# LCD.net
KiCad netlist of a schematic drawn in Altium Designer
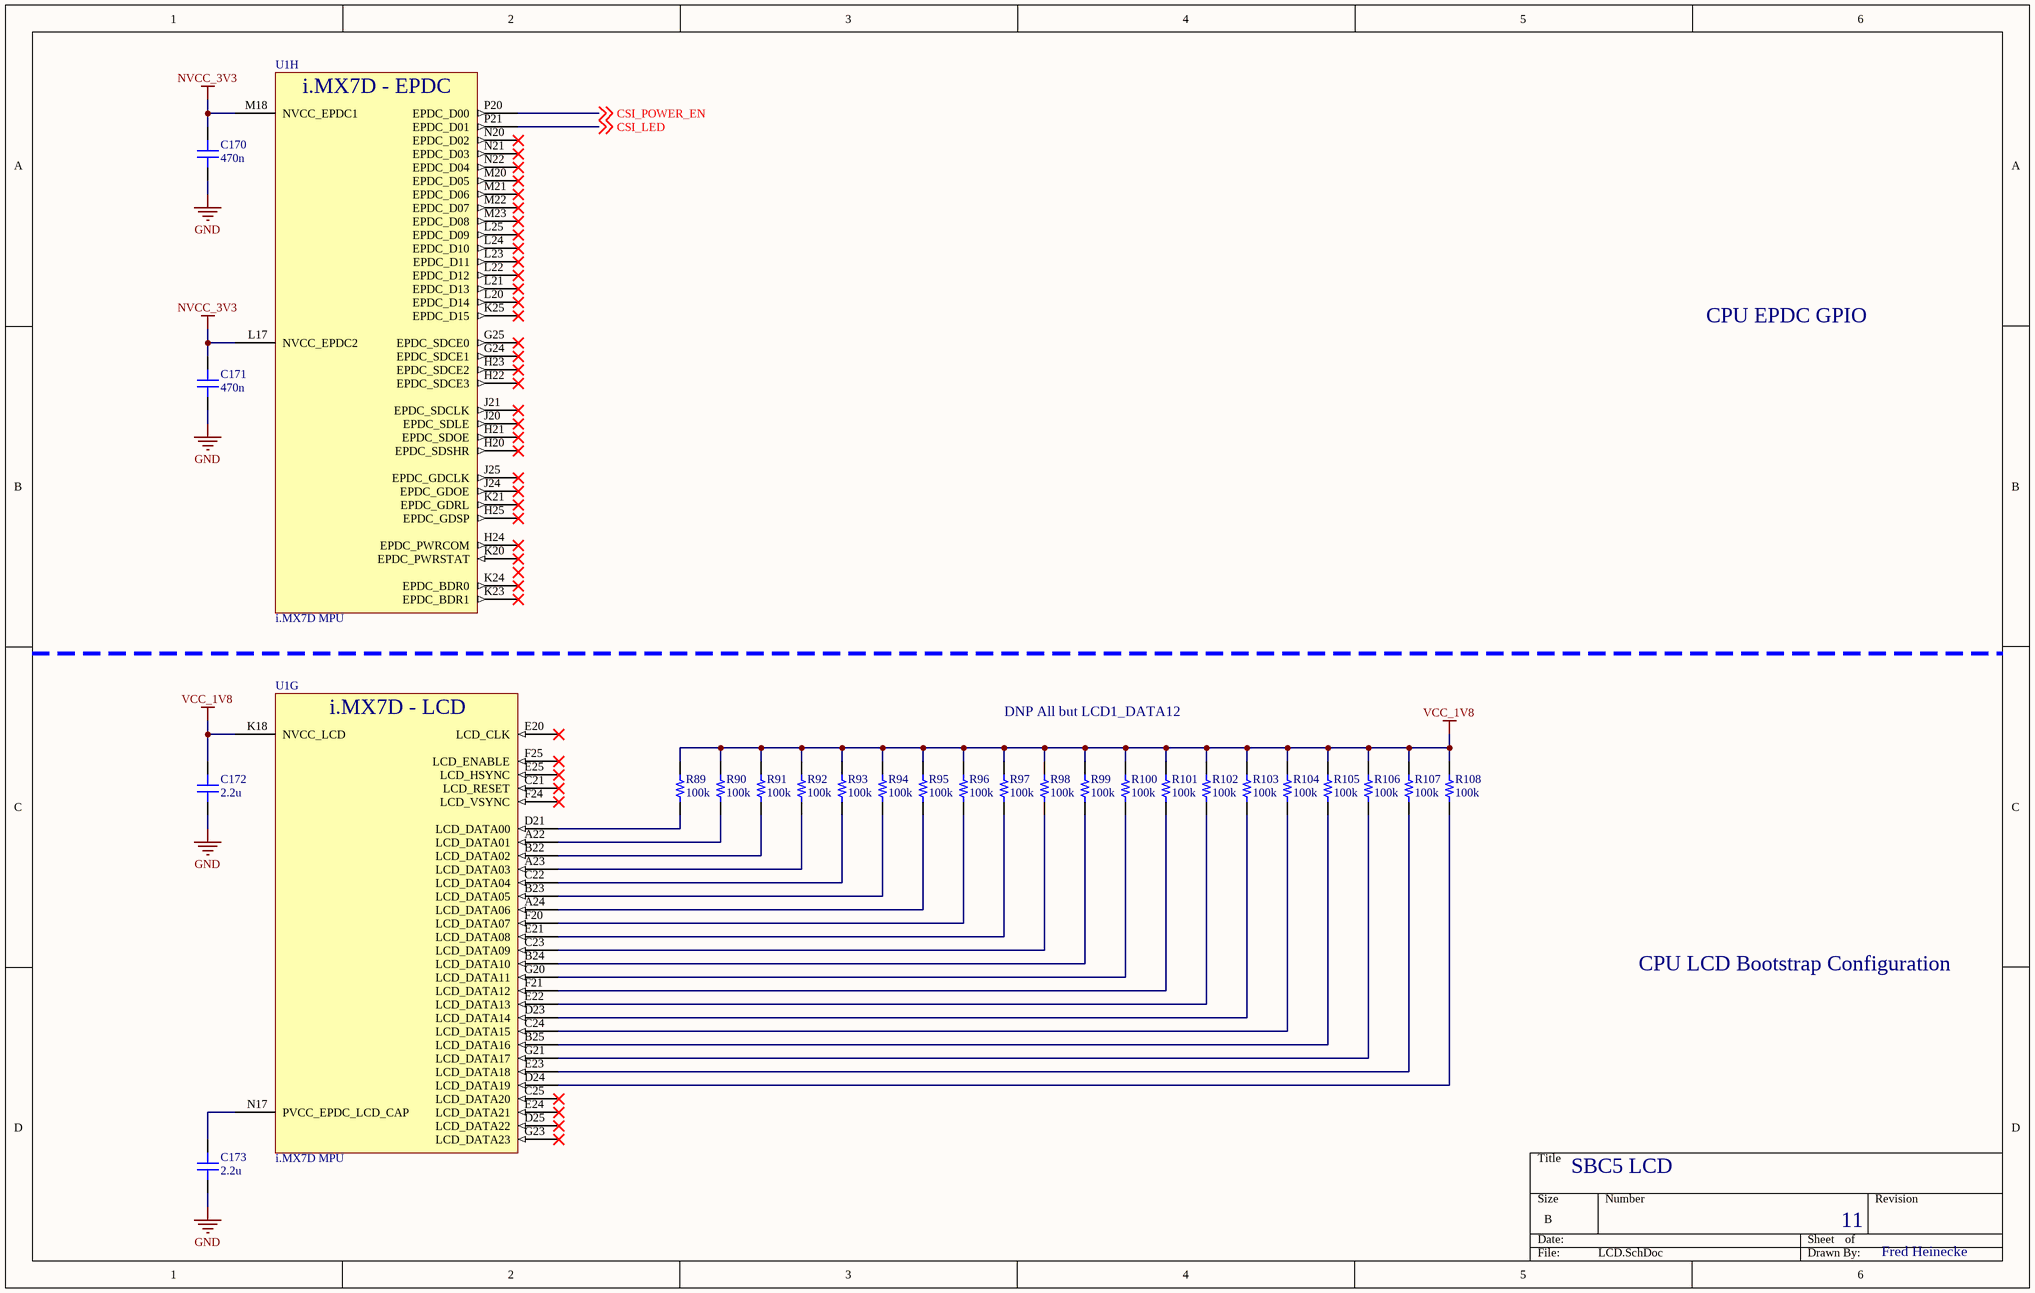
[diagram p0: LCD.SchDoc]

(export (version "E")
  (design (tool "Eeschema 10.0.6"))
  (components
    (comp (ref "C170")
      (value "470n")
      (footprint "C0402")
      (description "Cap Ceramic 0.47uF 10V X5R 10% SMD 0402 85C T/R")
      (fields
        (field (name "MANUFACTURER") "Samsung")
        (field (name "MANUFACTURER PART NUMBER") "CL05A474KP5NNNC")
      )
      (libsource (lib "SBC5") (part "CL05A474KP5NNNC"))
    )
    (comp (ref "C171")
      (value "470n")
      (footprint "C0402")
      (description "Cap Ceramic 0.47uF 10V X5R 10% SMD 0402 85C T/R")
      (fields
        (field (name "MANUFACTURER") "Samsung")
        (field (name "MANUFACTURER PART NUMBER") "CL05A474KP5NNNC")
      )
      (libsource (lib "SBC5") (part "CL05A474KP5NNNC"))
    )
    (comp (ref "C172")
      (value "2.2u")
      (footprint "C0402")
      (description "TAIYO YUDEN         LMK105BJ225MV-F            CERAMIC CAPACITOR, 2.2UF, 10V, X5R, 20%, 0402")
      (fields
        (field (name "MANUFACTURER") "Taiyo Yuden")
        (field (name "MANUFACTURER PART NUMBER") "LMK105BJ225MV-F")
      )
      (libsource (lib "SBC5") (part "LMK105BJ225MV-F"))
    )
    (comp (ref "C173")
      (value "2.2u")
      (footprint "C0402")
      (description "TAIYO YUDEN         LMK105BJ225MV-F            CERAMIC CAPACITOR, 2.2UF, 10V, X5R, 20%, 0402")
      (fields
        (field (name "MANUFACTURER") "Taiyo Yuden")
        (field (name "MANUFACTURER PART NUMBER") "LMK105BJ225MV-F")
      )
      (libsource (lib "SBC5") (part "LMK105BJ225MV-F"))
    )
    (comp (ref "R89")
      (value "100k")
      (footprint "R0201")
      (description "PANASONIC - ERJ1GNF1003C - RES, 100K, 1%, 0.05W, 0201, THICK FILM")
      (fields
        (field (name "MANUFACTURER") "Panasonic")
        (field (name "MANUFACTURER PART NUMBER") "ERJ-1GNF1003C")
      )
      (libsource (lib "SBC5") (part "ERJ-1GNF1003C"))
    )
    (comp (ref "R90")
      (value "100k")
      (footprint "R0201")
      (description "PANASONIC - ERJ1GNF1003C - RES, 100K, 1%, 0.05W, 0201, THICK FILM")
      (fields
        (field (name "MANUFACTURER") "Panasonic")
        (field (name "MANUFACTURER PART NUMBER") "ERJ-1GNF1003C")
      )
      (libsource (lib "SBC5") (part "ERJ-1GNF1003C"))
    )
    (comp (ref "R91")
      (value "100k")
      (footprint "R0201")
      (description "PANASONIC - ERJ1GNF1003C - RES, 100K, 1%, 0.05W, 0201, THICK FILM")
      (fields
        (field (name "MANUFACTURER") "Panasonic")
        (field (name "MANUFACTURER PART NUMBER") "ERJ-1GNF1003C")
      )
      (libsource (lib "SBC5") (part "ERJ-1GNF1003C"))
    )
    (comp (ref "R92")
      (value "100k")
      (footprint "R0201")
      (description "PANASONIC - ERJ1GNF1003C - RES, 100K, 1%, 0.05W, 0201, THICK FILM")
      (fields
        (field (name "MANUFACTURER") "Panasonic")
        (field (name "MANUFACTURER PART NUMBER") "ERJ-1GNF1003C")
      )
      (libsource (lib "SBC5") (part "ERJ-1GNF1003C"))
    )
    (comp (ref "R93")
      (value "100k")
      (footprint "R0201")
      (description "PANASONIC - ERJ1GNF1003C - RES, 100K, 1%, 0.05W, 0201, THICK FILM")
      (fields
        (field (name "MANUFACTURER") "Panasonic")
        (field (name "MANUFACTURER PART NUMBER") "ERJ-1GNF1003C")
      )
      (libsource (lib "SBC5") (part "ERJ-1GNF1003C"))
    )
    (comp (ref "R94")
      (value "100k")
      (footprint "R0201")
      (description "PANASONIC - ERJ1GNF1003C - RES, 100K, 1%, 0.05W, 0201, THICK FILM")
      (fields
        (field (name "MANUFACTURER") "Panasonic")
        (field (name "MANUFACTURER PART NUMBER") "ERJ-1GNF1003C")
      )
      (libsource (lib "SBC5") (part "ERJ-1GNF1003C"))
    )
    (comp (ref "R95")
      (value "100k")
      (footprint "R0201")
      (description "PANASONIC - ERJ1GNF1003C - RES, 100K, 1%, 0.05W, 0201, THICK FILM")
      (fields
        (field (name "MANUFACTURER") "Panasonic")
        (field (name "MANUFACTURER PART NUMBER") "ERJ-1GNF1003C")
      )
      (libsource (lib "SBC5") (part "ERJ-1GNF1003C"))
    )
    (comp (ref "R96")
      (value "100k")
      (footprint "R0201")
      (description "PANASONIC - ERJ1GNF1003C - RES, 100K, 1%, 0.05W, 0201, THICK FILM")
      (fields
        (field (name "MANUFACTURER") "Panasonic")
        (field (name "MANUFACTURER PART NUMBER") "ERJ-1GNF1003C")
      )
      (libsource (lib "SBC5") (part "ERJ-1GNF1003C"))
    )
    (comp (ref "R97")
      (value "100k")
      (footprint "R0201")
      (description "PANASONIC - ERJ1GNF1003C - RES, 100K, 1%, 0.05W, 0201, THICK FILM")
      (fields
        (field (name "MANUFACTURER") "Panasonic")
        (field (name "MANUFACTURER PART NUMBER") "ERJ-1GNF1003C")
      )
      (libsource (lib "SBC5") (part "ERJ-1GNF1003C"))
    )
    (comp (ref "R98")
      (value "100k")
      (footprint "R0201")
      (description "PANASONIC - ERJ1GNF1003C - RES, 100K, 1%, 0.05W, 0201, THICK FILM")
      (fields
        (field (name "MANUFACTURER") "Panasonic")
        (field (name "MANUFACTURER PART NUMBER") "ERJ-1GNF1003C")
      )
      (libsource (lib "SBC5") (part "ERJ-1GNF1003C"))
    )
    (comp (ref "R99")
      (value "100k")
      (footprint "R0201")
      (description "PANASONIC - ERJ1GNF1003C - RES, 100K, 1%, 0.05W, 0201, THICK FILM")
      (fields
        (field (name "MANUFACTURER") "Panasonic")
        (field (name "MANUFACTURER PART NUMBER") "ERJ-1GNF1003C")
      )
      (libsource (lib "SBC5") (part "ERJ-1GNF1003C"))
    )
    (comp (ref "R100")
      (value "100k")
      (footprint "R0201")
      (description "PANASONIC - ERJ1GNF1003C - RES, 100K, 1%, 0.05W, 0201, THICK FILM")
      (fields
        (field (name "MANUFACTURER") "Panasonic")
        (field (name "MANUFACTURER PART NUMBER") "ERJ-1GNF1003C")
      )
      (libsource (lib "SBC5") (part "ERJ-1GNF1003C"))
    )
    (comp (ref "R101")
      (value "100k")
      (footprint "R0201")
      (description "PANASONIC - ERJ1GNF1003C - RES, 100K, 1%, 0.05W, 0201, THICK FILM")
      (fields
        (field (name "MANUFACTURER") "Panasonic")
        (field (name "MANUFACTURER PART NUMBER") "ERJ-1GNF1003C")
      )
      (libsource (lib "SBC5") (part "ERJ-1GNF1003C"))
    )
    (comp (ref "R102")
      (value "100k")
      (footprint "R0201")
      (description "PANASONIC - ERJ1GNF1003C - RES, 100K, 1%, 0.05W, 0201, THICK FILM")
      (fields
        (field (name "MANUFACTURER") "Panasonic")
        (field (name "MANUFACTURER PART NUMBER") "ERJ-1GNF1003C")
      )
      (libsource (lib "SBC5") (part "ERJ-1GNF1003C"))
    )
    (comp (ref "R103")
      (value "100k")
      (footprint "R0201")
      (description "PANASONIC - ERJ1GNF1003C - RES, 100K, 1%, 0.05W, 0201, THICK FILM")
      (fields
        (field (name "MANUFACTURER") "Panasonic")
        (field (name "MANUFACTURER PART NUMBER") "ERJ-1GNF1003C")
      )
      (libsource (lib "SBC5") (part "ERJ-1GNF1003C"))
    )
    (comp (ref "R104")
      (value "100k")
      (footprint "R0201")
      (description "PANASONIC - ERJ1GNF1003C - RES, 100K, 1%, 0.05W, 0201, THICK FILM")
      (fields
        (field (name "MANUFACTURER") "Panasonic")
        (field (name "MANUFACTURER PART NUMBER") "ERJ-1GNF1003C")
      )
      (libsource (lib "SBC5") (part "ERJ-1GNF1003C"))
    )
    (comp (ref "R105")
      (value "100k")
      (footprint "R0201")
      (description "PANASONIC - ERJ1GNF1003C - RES, 100K, 1%, 0.05W, 0201, THICK FILM")
      (fields
        (field (name "MANUFACTURER") "Panasonic")
        (field (name "MANUFACTURER PART NUMBER") "ERJ-1GNF1003C")
      )
      (libsource (lib "SBC5") (part "ERJ-1GNF1003C"))
    )
    (comp (ref "R106")
      (value "100k")
      (footprint "R0201")
      (description "PANASONIC - ERJ1GNF1003C - RES, 100K, 1%, 0.05W, 0201, THICK FILM")
      (fields
        (field (name "MANUFACTURER") "Panasonic")
        (field (name "MANUFACTURER PART NUMBER") "ERJ-1GNF1003C")
      )
      (libsource (lib "SBC5") (part "ERJ-1GNF1003C"))
    )
    (comp (ref "R107")
      (value "100k")
      (footprint "R0201")
      (description "PANASONIC - ERJ1GNF1003C - RES, 100K, 1%, 0.05W, 0201, THICK FILM")
      (fields
        (field (name "MANUFACTURER") "Panasonic")
        (field (name "MANUFACTURER PART NUMBER") "ERJ-1GNF1003C")
      )
      (libsource (lib "SBC5") (part "ERJ-1GNF1003C"))
    )
    (comp (ref "R108")
      (value "100k")
      (footprint "R0201")
      (description "PANASONIC - ERJ1GNF1003C - RES, 100K, 1%, 0.05W, 0201, THICK FILM")
      (fields
        (field (name "MANUFACTURER") "Panasonic")
        (field (name "MANUFACTURER PART NUMBER") "ERJ-1GNF1003C")
      )
      (libsource (lib "SBC5") (part "ERJ-1GNF1003C"))
    )
    (comp (ref "U1")
      (value "i.MX7D MPU")
      (footprint "BGA541C75P25X25_1900X1900X140")
      (description "Heterogeneous Multicore Processing Architecture")
      (fields
        (field (name "MANUFACTURER") "NXP Freescale")
        (field (name "MANUFACTURER PART NUMBER") "MCIMX7D2DVM12SD")
      )
      (libsource (lib "SBC5") (part "MCIMX7D2DVM12SD"))
    )
  )
  (nets
    (net (code "1") (name "CSI_LED") (class "Default")
      (node (ref "U1") (pin "P21") (pinfunction "EPDC_D01_P21") (pintype "output"))
    )
    (net (code "2") (name "CSI_POWER_EN") (class "Default")
      (node (ref "U1") (pin "P20") (pinfunction "EPDC_D00_P20") (pintype "output"))
    )
    (net (code "3") (name "GND") (class "Default")
      (node (ref "C170") (pin "1") (pinfunction "1_1") (pintype "passive"))
      (node (ref "C171") (pin "1") (pinfunction "1_1") (pintype "passive"))
      (node (ref "C172") (pin "1") (pinfunction "1_1") (pintype "passive"))
      (node (ref "C173") (pin "1") (pinfunction "1_1") (pintype "passive"))
    )
    (net (code "4") (name "NVCC_3V3") (class "Default")
      (node (ref "C170") (pin "2") (pinfunction "2_2") (pintype "passive"))
      (node (ref "C171") (pin "2") (pinfunction "2_2") (pintype "passive"))
      (node (ref "U1") (pin "L17") (pinfunction "NVCC_EPDC2_L17") (pintype "power_in"))
      (node (ref "U1") (pin "M18") (pinfunction "NVCC_EPDC1_M18") (pintype "power_in"))
    )
    (net (code "5") (name "Net-(U1G-LCD_DATA00)") (class "Default")
      (node (ref "R89") (pin "1") (pinfunction "1_1") (pintype "passive"))
      (node (ref "U1") (pin "D21") (pinfunction "LCD_DATA00_D21") (pintype "input"))
    )
    (net (code "6") (name "Net-(U1G-LCD_DATA01)") (class "Default")
      (node (ref "R90") (pin "1") (pinfunction "1_1") (pintype "passive"))
      (node (ref "U1") (pin "A22") (pinfunction "LCD_DATA01_A22") (pintype "input"))
    )
    (net (code "7") (name "Net-(U1G-LCD_DATA02)") (class "Default")
      (node (ref "R91") (pin "1") (pinfunction "1_1") (pintype "passive"))
      (node (ref "U1") (pin "B22") (pinfunction "LCD_DATA02_B22") (pintype "input"))
    )
    (net (code "8") (name "Net-(U1G-LCD_DATA03)") (class "Default")
      (node (ref "R92") (pin "1") (pinfunction "1_1") (pintype "passive"))
      (node (ref "U1") (pin "A23") (pinfunction "LCD_DATA03_A23") (pintype "input"))
    )
    (net (code "9") (name "Net-(U1G-LCD_DATA04)") (class "Default")
      (node (ref "R93") (pin "1") (pinfunction "1_1") (pintype "passive"))
      (node (ref "U1") (pin "C22") (pinfunction "LCD_DATA04_C22") (pintype "input"))
    )
    (net (code "10") (name "Net-(U1G-LCD_DATA05)") (class "Default")
      (node (ref "R94") (pin "1") (pinfunction "1_1") (pintype "passive"))
      (node (ref "U1") (pin "B23") (pinfunction "LCD_DATA05_B23") (pintype "input"))
    )
    (net (code "11") (name "Net-(U1G-LCD_DATA06)") (class "Default")
      (node (ref "R95") (pin "1") (pinfunction "1_1") (pintype "passive"))
      (node (ref "U1") (pin "A24") (pinfunction "LCD_DATA06_A24") (pintype "input"))
    )
    (net (code "12") (name "Net-(U1G-LCD_DATA07)") (class "Default")
      (node (ref "R96") (pin "1") (pinfunction "1_1") (pintype "passive"))
      (node (ref "U1") (pin "F20") (pinfunction "LCD_DATA07_F20") (pintype "input"))
    )
    (net (code "13") (name "Net-(U1G-LCD_DATA08)") (class "Default")
      (node (ref "R97") (pin "1") (pinfunction "1_1") (pintype "passive"))
      (node (ref "U1") (pin "E21") (pinfunction "LCD_DATA08_E21") (pintype "input"))
    )
    (net (code "14") (name "Net-(U1G-LCD_DATA09)") (class "Default")
      (node (ref "R98") (pin "1") (pinfunction "1_1") (pintype "passive"))
      (node (ref "U1") (pin "C23") (pinfunction "LCD_DATA09_C23") (pintype "input"))
    )
    (net (code "15") (name "Net-(U1G-LCD_DATA10)") (class "Default")
      (node (ref "R99") (pin "1") (pinfunction "1_1") (pintype "passive"))
      (node (ref "U1") (pin "B24") (pinfunction "LCD_DATA10_B24") (pintype "input"))
    )
    (net (code "16") (name "Net-(U1G-LCD_DATA11)") (class "Default")
      (node (ref "R100") (pin "1") (pinfunction "1_1") (pintype "passive"))
      (node (ref "U1") (pin "G20") (pinfunction "LCD_DATA11_G20") (pintype "input"))
    )
    (net (code "17") (name "Net-(U1G-LCD_DATA12)") (class "Default")
      (node (ref "R101") (pin "1") (pinfunction "1_1") (pintype "passive"))
      (node (ref "U1") (pin "F21") (pinfunction "LCD_DATA12_F21") (pintype "input"))
    )
    (net (code "18") (name "Net-(U1G-LCD_DATA13)") (class "Default")
      (node (ref "R102") (pin "1") (pinfunction "1_1") (pintype "passive"))
      (node (ref "U1") (pin "E22") (pinfunction "LCD_DATA13_E22") (pintype "input"))
    )
    (net (code "19") (name "Net-(U1G-LCD_DATA14)") (class "Default")
      (node (ref "R103") (pin "1") (pinfunction "1_1") (pintype "passive"))
      (node (ref "U1") (pin "D23") (pinfunction "LCD_DATA14_D23") (pintype "input"))
    )
    (net (code "20") (name "Net-(U1G-LCD_DATA15)") (class "Default")
      (node (ref "R104") (pin "1") (pinfunction "1_1") (pintype "passive"))
      (node (ref "U1") (pin "C24") (pinfunction "LCD_DATA15_C24") (pintype "input"))
    )
    (net (code "21") (name "Net-(U1G-LCD_DATA16)") (class "Default")
      (node (ref "R105") (pin "1") (pinfunction "1_1") (pintype "passive"))
      (node (ref "U1") (pin "B25") (pinfunction "LCD_DATA16_B25") (pintype "input"))
    )
    (net (code "22") (name "Net-(U1G-LCD_DATA17)") (class "Default")
      (node (ref "R106") (pin "1") (pinfunction "1_1") (pintype "passive"))
      (node (ref "U1") (pin "G21") (pinfunction "LCD_DATA17_G21") (pintype "input"))
    )
    (net (code "23") (name "Net-(U1G-LCD_DATA18)") (class "Default")
      (node (ref "R107") (pin "1") (pinfunction "1_1") (pintype "passive"))
      (node (ref "U1") (pin "E23") (pinfunction "LCD_DATA18_E23") (pintype "input"))
    )
    (net (code "24") (name "Net-(U1G-LCD_DATA19)") (class "Default")
      (node (ref "R108") (pin "1") (pinfunction "1_1") (pintype "passive"))
      (node (ref "U1") (pin "D24") (pinfunction "LCD_DATA19_D24") (pintype "input"))
    )
    (net (code "25") (name "Net-(U1G-PVCC_EPDC_LCD_CAP)") (class "Default")
      (node (ref "C173") (pin "2") (pinfunction "2_2") (pintype "passive"))
      (node (ref "U1") (pin "N17") (pinfunction "PVCC_EPDC_LCD_CAP_N17") (pintype "power_in"))
    )
    (net (code "26") (name "VCC_1V8") (class "Default")
      (node (ref "C172") (pin "2") (pinfunction "2_2") (pintype "passive"))
      (node (ref "R100") (pin "2") (pinfunction "2_2") (pintype "passive"))
      (node (ref "R101") (pin "2") (pinfunction "2_2") (pintype "passive"))
      (node (ref "R102") (pin "2") (pinfunction "2_2") (pintype "passive"))
      (node (ref "R103") (pin "2") (pinfunction "2_2") (pintype "passive"))
      (node (ref "R104") (pin "2") (pinfunction "2_2") (pintype "passive"))
      (node (ref "R105") (pin "2") (pinfunction "2_2") (pintype "passive"))
      (node (ref "R106") (pin "2") (pinfunction "2_2") (pintype "passive"))
      (node (ref "R107") (pin "2") (pinfunction "2_2") (pintype "passive"))
      (node (ref "R108") (pin "2") (pinfunction "2_2") (pintype "passive"))
      (node (ref "R89") (pin "2") (pinfunction "2_2") (pintype "passive"))
      (node (ref "R90") (pin "2") (pinfunction "2_2") (pintype "passive"))
      (node (ref "R91") (pin "2") (pinfunction "2_2") (pintype "passive"))
      (node (ref "R92") (pin "2") (pinfunction "2_2") (pintype "passive"))
      (node (ref "R93") (pin "2") (pinfunction "2_2") (pintype "passive"))
      (node (ref "R94") (pin "2") (pinfunction "2_2") (pintype "passive"))
      (node (ref "R95") (pin "2") (pinfunction "2_2") (pintype "passive"))
      (node (ref "R96") (pin "2") (pinfunction "2_2") (pintype "passive"))
      (node (ref "R97") (pin "2") (pinfunction "2_2") (pintype "passive"))
      (node (ref "R98") (pin "2") (pinfunction "2_2") (pintype "passive"))
      (node (ref "R99") (pin "2") (pinfunction "2_2") (pintype "passive"))
      (node (ref "U1") (pin "K18") (pinfunction "NVCC_LCD_K18") (pintype "power_in"))
    )
    (net (code "27") (name "unconnected-(U1G-LCD_CLK-PadE20)") (class "Default")
      (node (ref "U1") (pin "E20") (pinfunction "LCD_CLK_E20") (pintype "input+no_connect"))
    )
    (net (code "28") (name "unconnected-(U1G-LCD_DATA20-PadC25)") (class "Default")
      (node (ref "U1") (pin "C25") (pinfunction "LCD_DATA20_C25") (pintype "input+no_connect"))
    )
    (net (code "29") (name "unconnected-(U1G-LCD_DATA21-PadE24)") (class "Default")
      (node (ref "U1") (pin "E24") (pinfunction "LCD_DATA21_E24") (pintype "input+no_connect"))
    )
    (net (code "30") (name "unconnected-(U1G-LCD_DATA22-PadD25)") (class "Default")
      (node (ref "U1") (pin "D25") (pinfunction "LCD_DATA22_D25") (pintype "input+no_connect"))
    )
    (net (code "31") (name "unconnected-(U1G-LCD_DATA23-PadG23)") (class "Default")
      (node (ref "U1") (pin "G23") (pinfunction "LCD_DATA23_G23") (pintype "input+no_connect"))
    )
    (net (code "32") (name "unconnected-(U1G-LCD_ENABLE-PadF25)") (class "Default")
      (node (ref "U1") (pin "F25") (pinfunction "LCD_ENABLE_F25") (pintype "input+no_connect"))
    )
    (net (code "33") (name "unconnected-(U1G-LCD_HSYNC-PadE25)") (class "Default")
      (node (ref "U1") (pin "E25") (pinfunction "LCD_HSYNC_E25") (pintype "input+no_connect"))
    )
    (net (code "34") (name "unconnected-(U1G-LCD_RESET-PadC21)") (class "Default")
      (node (ref "U1") (pin "C21") (pinfunction "LCD_RESET_C21") (pintype "input+no_connect"))
    )
    (net (code "35") (name "unconnected-(U1G-LCD_VSYNC-PadF24)") (class "Default")
      (node (ref "U1") (pin "F24") (pinfunction "LCD_VSYNC_F24") (pintype "input+no_connect"))
    )
    (net (code "36") (name "unconnected-(U1H-EPDC_BDR0-PadK24)") (class "Default")
      (node (ref "U1") (pin "K24") (pinfunction "EPDC_BDR0_K24") (pintype "output+no_connect"))
    )
    (net (code "37") (name "unconnected-(U1H-EPDC_BDR1-PadK23)") (class "Default")
      (node (ref "U1") (pin "K23") (pinfunction "EPDC_BDR1_K23") (pintype "output+no_connect"))
    )
    (net (code "38") (name "unconnected-(U1H-EPDC_D02-PadN20)") (class "Default")
      (node (ref "U1") (pin "N20") (pinfunction "EPDC_D02_N20") (pintype "output+no_connect"))
    )
    (net (code "39") (name "unconnected-(U1H-EPDC_D03-PadN21)") (class "Default")
      (node (ref "U1") (pin "N21") (pinfunction "EPDC_D03_N21") (pintype "output+no_connect"))
    )
    (net (code "40") (name "unconnected-(U1H-EPDC_D04-PadN22)") (class "Default")
      (node (ref "U1") (pin "N22") (pinfunction "EPDC_D04_N22") (pintype "output+no_connect"))
    )
    (net (code "41") (name "unconnected-(U1H-EPDC_D05-PadM20)") (class "Default")
      (node (ref "U1") (pin "M20") (pinfunction "EPDC_D05_M20") (pintype "output+no_connect"))
    )
    (net (code "42") (name "unconnected-(U1H-EPDC_D06-PadM21)") (class "Default")
      (node (ref "U1") (pin "M21") (pinfunction "EPDC_D06_M21") (pintype "output+no_connect"))
    )
    (net (code "43") (name "unconnected-(U1H-EPDC_D07-PadM22)") (class "Default")
      (node (ref "U1") (pin "M22") (pinfunction "EPDC_D07_M22") (pintype "output+no_connect"))
    )
    (net (code "44") (name "unconnected-(U1H-EPDC_D08-PadM23)") (class "Default")
      (node (ref "U1") (pin "M23") (pinfunction "EPDC_D08_M23") (pintype "output+no_connect"))
    )
    (net (code "45") (name "unconnected-(U1H-EPDC_D09-PadL25)") (class "Default")
      (node (ref "U1") (pin "L25") (pinfunction "EPDC_D09_L25") (pintype "output+no_connect"))
    )
    (net (code "46") (name "unconnected-(U1H-EPDC_D10-PadL24)") (class "Default")
      (node (ref "U1") (pin "L24") (pinfunction "EPDC_D10_L24") (pintype "output+no_connect"))
    )
    (net (code "47") (name "unconnected-(U1H-EPDC_D11-PadL23)") (class "Default")
      (node (ref "U1") (pin "L23") (pinfunction "EPDC_D11_L23") (pintype "output+no_connect"))
    )
    (net (code "48") (name "unconnected-(U1H-EPDC_D12-PadL22)") (class "Default")
      (node (ref "U1") (pin "L22") (pinfunction "EPDC_D12_L22") (pintype "output+no_connect"))
    )
    (net (code "49") (name "unconnected-(U1H-EPDC_D13-PadL21)") (class "Default")
      (node (ref "U1") (pin "L21") (pinfunction "EPDC_D13_L21") (pintype "output+no_connect"))
    )
    (net (code "50") (name "unconnected-(U1H-EPDC_D14-PadL20)") (class "Default")
      (node (ref "U1") (pin "L20") (pinfunction "EPDC_D14_L20") (pintype "output+no_connect"))
    )
    (net (code "51") (name "unconnected-(U1H-EPDC_D15-PadK25)") (class "Default")
      (node (ref "U1") (pin "K25") (pinfunction "EPDC_D15_K25") (pintype "output+no_connect"))
    )
    (net (code "52") (name "unconnected-(U1H-EPDC_GDCLK-PadJ25)") (class "Default")
      (node (ref "U1") (pin "J25") (pinfunction "EPDC_GDCLK_J25") (pintype "output+no_connect"))
    )
    (net (code "53") (name "unconnected-(U1H-EPDC_GDOE-PadJ24)") (class "Default")
      (node (ref "U1") (pin "J24") (pinfunction "EPDC_GDOE_J24") (pintype "output+no_connect"))
    )
    (net (code "54") (name "unconnected-(U1H-EPDC_GDRL-PadK21)") (class "Default")
      (node (ref "U1") (pin "K21") (pinfunction "EPDC_GDRL_K21") (pintype "output+no_connect"))
    )
    (net (code "55") (name "unconnected-(U1H-EPDC_GDSP-PadH25)") (class "Default")
      (node (ref "U1") (pin "H25") (pinfunction "EPDC_GDSP_H25") (pintype "output+no_connect"))
    )
    (net (code "56") (name "unconnected-(U1H-EPDC_PWRCOM-PadH24)") (class "Default")
      (node (ref "U1") (pin "H24") (pinfunction "EPDC_PWRCOM_H24") (pintype "output+no_connect"))
    )
    (net (code "57") (name "unconnected-(U1H-EPDC_PWRSTAT-PadK20)") (class "Default")
      (node (ref "U1") (pin "K20") (pinfunction "EPDC_PWRSTAT_K20") (pintype "input+no_connect"))
    )
    (net (code "58") (name "unconnected-(U1H-EPDC_SDCE0-PadG25)") (class "Default")
      (node (ref "U1") (pin "G25") (pinfunction "EPDC_SDCE0_G25") (pintype "output+no_connect"))
    )
    (net (code "59") (name "unconnected-(U1H-EPDC_SDCE1-PadG24)") (class "Default")
      (node (ref "U1") (pin "G24") (pinfunction "EPDC_SDCE1_G24") (pintype "output+no_connect"))
    )
    (net (code "60") (name "unconnected-(U1H-EPDC_SDCE2-PadH23)") (class "Default")
      (node (ref "U1") (pin "H23") (pinfunction "EPDC_SDCE2_H23") (pintype "output+no_connect"))
    )
    (net (code "61") (name "unconnected-(U1H-EPDC_SDCE3-PadH22)") (class "Default")
      (node (ref "U1") (pin "H22") (pinfunction "EPDC_SDCE3_H22") (pintype "output+no_connect"))
    )
    (net (code "62") (name "unconnected-(U1H-EPDC_SDCLK-PadJ21)") (class "Default")
      (node (ref "U1") (pin "J21") (pinfunction "EPDC_SDCLK_J21") (pintype "output+no_connect"))
    )
    (net (code "63") (name "unconnected-(U1H-EPDC_SDLE-PadJ20)") (class "Default")
      (node (ref "U1") (pin "J20") (pinfunction "EPDC_SDLE_J20") (pintype "output+no_connect"))
    )
    (net (code "64") (name "unconnected-(U1H-EPDC_SDOE-PadH21)") (class "Default")
      (node (ref "U1") (pin "H21") (pinfunction "EPDC_SDOE_H21") (pintype "output+no_connect"))
    )
    (net (code "65") (name "unconnected-(U1H-EPDC_SDSHR-PadH20)") (class "Default")
      (node (ref "U1") (pin "H20") (pinfunction "EPDC_SDSHR_H20") (pintype "output+no_connect"))
    )
  )
)
